# FPGA_Ground.net
KiCad netlist of a schematic drawn in Altium Designer
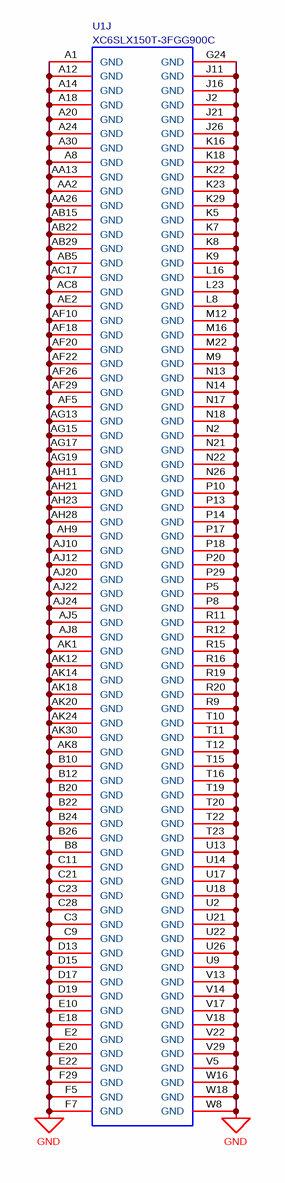
[diagram p0: FPGA_Ground.SchDoc]

(export (version "E")
  (design (tool "Eeschema 10.0.6"))
  (components
    (comp (ref "U1")
      (value "XC6SLX150T-3FGG900C")
      (footprint "MC_S6/BGA/FGG900")
      (fields (field (name "MANUFACTURER") "Xilinx Inc."))
      (libsource (lib "ALCT_MEZ_SPARTAN6_Library") (part "XC6SLX150T-3FGG900C"))
    )
  )
  (nets
    (net (code "1") (name "GND") (class "Default")
      (node (ref "U1") (pin "A1") (pinfunction "GND_A1") (pintype "power_in"))
      (node (ref "U1") (pin "A12") (pinfunction "GND_A12") (pintype "power_in"))
      (node (ref "U1") (pin "A14") (pinfunction "GND_A14") (pintype "power_in"))
      (node (ref "U1") (pin "A18") (pinfunction "GND_A18") (pintype "power_in"))
      (node (ref "U1") (pin "A20") (pinfunction "GND_A20") (pintype "power_in"))
      (node (ref "U1") (pin "A24") (pinfunction "GND_A24") (pintype "power_in"))
      (node (ref "U1") (pin "A30") (pinfunction "GND_A30") (pintype "power_in"))
      (node (ref "U1") (pin "A8") (pinfunction "GND_A8") (pintype "power_in"))
      (node (ref "U1") (pin "AA13") (pinfunction "GND_AA13") (pintype "power_in"))
      (node (ref "U1") (pin "AA2") (pinfunction "GND_AA2") (pintype "power_in"))
      (node (ref "U1") (pin "AA26") (pinfunction "GND_AA26") (pintype "power_in"))
      (node (ref "U1") (pin "AB15") (pinfunction "GND_AB15") (pintype "power_in"))
      (node (ref "U1") (pin "AB22") (pinfunction "GND_AB22") (pintype "power_in"))
      (node (ref "U1") (pin "AB29") (pinfunction "GND_AB29") (pintype "power_in"))
      (node (ref "U1") (pin "AB5") (pinfunction "GND_AB5") (pintype "power_in"))
      (node (ref "U1") (pin "AC17") (pinfunction "GND_AC17") (pintype "power_in"))
      (node (ref "U1") (pin "AC8") (pinfunction "GND_AC8") (pintype "power_in"))
      (node (ref "U1") (pin "AE2") (pinfunction "GND_AE2") (pintype "power_in"))
      (node (ref "U1") (pin "AF10") (pinfunction "GND_AF10") (pintype "power_in"))
      (node (ref "U1") (pin "AF18") (pinfunction "GND_AF18") (pintype "power_in"))
      (node (ref "U1") (pin "AF20") (pinfunction "GND_AF20") (pintype "power_in"))
      (node (ref "U1") (pin "AF22") (pinfunction "GND_AF22") (pintype "power_in"))
      (node (ref "U1") (pin "AF26") (pinfunction "GND_AF26") (pintype "power_in"))
      (node (ref "U1") (pin "AF29") (pinfunction "GND_AF29") (pintype "power_in"))
      (node (ref "U1") (pin "AF5") (pinfunction "GND_AF5") (pintype "power_in"))
      (node (ref "U1") (pin "AG13") (pinfunction "GND_AG13") (pintype "power_in"))
      (node (ref "U1") (pin "AG15") (pinfunction "GND_AG15") (pintype "power_in"))
      (node (ref "U1") (pin "AG17") (pinfunction "GND_AG17") (pintype "power_in"))
      (node (ref "U1") (pin "AG19") (pinfunction "GND_AG19") (pintype "power_in"))
      (node (ref "U1") (pin "AH11") (pinfunction "GND_AH11") (pintype "power_in"))
      (node (ref "U1") (pin "AH21") (pinfunction "GND_AH21") (pintype "power_in"))
      (node (ref "U1") (pin "AH23") (pinfunction "GND_AH23") (pintype "power_in"))
      (node (ref "U1") (pin "AH28") (pinfunction "GND_AH28") (pintype "power_in"))
      (node (ref "U1") (pin "AH9") (pinfunction "GND_AH9") (pintype "power_in"))
      (node (ref "U1") (pin "AJ10") (pinfunction "GND_AJ10") (pintype "power_in"))
      (node (ref "U1") (pin "AJ12") (pinfunction "GND_AJ12") (pintype "power_in"))
      (node (ref "U1") (pin "AJ20") (pinfunction "GND_AJ20") (pintype "power_in"))
      (node (ref "U1") (pin "AJ22") (pinfunction "GND_AJ22") (pintype "power_in"))
      (node (ref "U1") (pin "AJ24") (pinfunction "GND_AJ24") (pintype "power_in"))
      (node (ref "U1") (pin "AJ5") (pinfunction "GND_AJ5") (pintype "power_in"))
      (node (ref "U1") (pin "AJ8") (pinfunction "GND_AJ8") (pintype "power_in"))
      (node (ref "U1") (pin "AK1") (pinfunction "GND_AK1") (pintype "power_in"))
      (node (ref "U1") (pin "AK12") (pinfunction "GND_AK12") (pintype "power_in"))
      (node (ref "U1") (pin "AK14") (pinfunction "GND_AK14") (pintype "power_in"))
      (node (ref "U1") (pin "AK18") (pinfunction "GND_AK18") (pintype "power_in"))
      (node (ref "U1") (pin "AK20") (pinfunction "GND_AK20") (pintype "power_in"))
      (node (ref "U1") (pin "AK24") (pinfunction "GND_AK24") (pintype "power_in"))
      (node (ref "U1") (pin "AK30") (pinfunction "GND_AK30") (pintype "power_in"))
      (node (ref "U1") (pin "AK8") (pinfunction "GND_AK8") (pintype "power_in"))
      (node (ref "U1") (pin "B10") (pinfunction "GND_B10") (pintype "power_in"))
      (node (ref "U1") (pin "B12") (pinfunction "GND_B12") (pintype "power_in"))
      (node (ref "U1") (pin "B20") (pinfunction "GND_B20") (pintype "power_in"))
      (node (ref "U1") (pin "B22") (pinfunction "GND_B22") (pintype "power_in"))
      (node (ref "U1") (pin "B24") (pinfunction "GND_B24") (pintype "power_in"))
      (node (ref "U1") (pin "B26") (pinfunction "GND_B26") (pintype "power_in"))
      (node (ref "U1") (pin "B8") (pinfunction "GND_B8") (pintype "power_in"))
      (node (ref "U1") (pin "C11") (pinfunction "GND_C11") (pintype "power_in"))
      (node (ref "U1") (pin "C21") (pinfunction "GND_C21") (pintype "power_in"))
      (node (ref "U1") (pin "C23") (pinfunction "GND_C23") (pintype "power_in"))
      (node (ref "U1") (pin "C28") (pinfunction "GND_C28") (pintype "power_in"))
      (node (ref "U1") (pin "C3") (pinfunction "GND_C3") (pintype "power_in"))
      (node (ref "U1") (pin "C9") (pinfunction "GND_C9") (pintype "power_in"))
      (node (ref "U1") (pin "D13") (pinfunction "GND_D13") (pintype "power_in"))
      (node (ref "U1") (pin "D15") (pinfunction "GND_D15") (pintype "power_in"))
      (node (ref "U1") (pin "D17") (pinfunction "GND_D17") (pintype "power_in"))
      (node (ref "U1") (pin "D19") (pinfunction "GND_D19") (pintype "power_in"))
      (node (ref "U1") (pin "E10") (pinfunction "GND_E10") (pintype "power_in"))
      (node (ref "U1") (pin "E18") (pinfunction "GND_E18") (pintype "power_in"))
      (node (ref "U1") (pin "E2") (pinfunction "GND_E2") (pintype "power_in"))
      (node (ref "U1") (pin "E20") (pinfunction "GND_E20") (pintype "power_in"))
      (node (ref "U1") (pin "E22") (pinfunction "GND_E22") (pintype "power_in"))
      (node (ref "U1") (pin "F29") (pinfunction "GND_F29") (pintype "power_in"))
      (node (ref "U1") (pin "F5") (pinfunction "GND_F5") (pintype "power_in"))
      (node (ref "U1") (pin "F7") (pinfunction "GND_F7") (pintype "power_in"))
      (node (ref "U1") (pin "G24") (pinfunction "GND_G24") (pintype "power_in"))
      (node (ref "U1") (pin "J11") (pinfunction "GND_J11") (pintype "power_in"))
      (node (ref "U1") (pin "J16") (pinfunction "GND_J16") (pintype "power_in"))
      (node (ref "U1") (pin "J2") (pinfunction "GND_J2") (pintype "power_in"))
      (node (ref "U1") (pin "J21") (pinfunction "GND_J21") (pintype "power_in"))
      (node (ref "U1") (pin "J26") (pinfunction "GND_J26") (pintype "power_in"))
      (node (ref "U1") (pin "K16") (pinfunction "GND_K16") (pintype "power_in"))
      (node (ref "U1") (pin "K18") (pinfunction "GND_K18") (pintype "power_in"))
      (node (ref "U1") (pin "K22") (pinfunction "GND_K22") (pintype "power_in"))
      (node (ref "U1") (pin "K23") (pinfunction "GND_K23") (pintype "power_in"))
      (node (ref "U1") (pin "K29") (pinfunction "GND_K29") (pintype "power_in"))
      (node (ref "U1") (pin "K5") (pinfunction "GND_K5") (pintype "power_in"))
      (node (ref "U1") (pin "K7") (pinfunction "GND_K7") (pintype "power_in"))
      (node (ref "U1") (pin "K8") (pinfunction "GND_K8") (pintype "power_in"))
      (node (ref "U1") (pin "K9") (pinfunction "GND_K9") (pintype "power_in"))
      (node (ref "U1") (pin "L16") (pinfunction "GND_L16") (pintype "power_in"))
      (node (ref "U1") (pin "L23") (pinfunction "GND_L23") (pintype "power_in"))
      (node (ref "U1") (pin "L8") (pinfunction "GND_L8") (pintype "power_in"))
      (node (ref "U1") (pin "M12") (pinfunction "GND_M12") (pintype "power_in"))
      (node (ref "U1") (pin "M16") (pinfunction "GND_M16") (pintype "power_in"))
      (node (ref "U1") (pin "M22") (pinfunction "GND_M22") (pintype "power_in"))
      (node (ref "U1") (pin "M9") (pinfunction "GND_M9") (pintype "power_in"))
      (node (ref "U1") (pin "N13") (pinfunction "GND_N13") (pintype "power_in"))
      (node (ref "U1") (pin "N14") (pinfunction "GND_N14") (pintype "power_in"))
      (node (ref "U1") (pin "N17") (pinfunction "GND_N17") (pintype "power_in"))
      (node (ref "U1") (pin "N18") (pinfunction "GND_N18") (pintype "power_in"))
      (node (ref "U1") (pin "N2") (pinfunction "GND_N2") (pintype "power_in"))
      (node (ref "U1") (pin "N21") (pinfunction "GND_N21") (pintype "power_in"))
      (node (ref "U1") (pin "N22") (pinfunction "GND_N22") (pintype "power_in"))
      (node (ref "U1") (pin "N26") (pinfunction "GND_N26") (pintype "power_in"))
      (node (ref "U1") (pin "P10") (pinfunction "GND_P10") (pintype "power_in"))
      (node (ref "U1") (pin "P13") (pinfunction "GND_P13") (pintype "power_in"))
      (node (ref "U1") (pin "P14") (pinfunction "GND_P14") (pintype "power_in"))
      (node (ref "U1") (pin "P17") (pinfunction "GND_P17") (pintype "power_in"))
      (node (ref "U1") (pin "P18") (pinfunction "GND_P18") (pintype "power_in"))
      (node (ref "U1") (pin "P20") (pinfunction "GND_P20") (pintype "power_in"))
      (node (ref "U1") (pin "P29") (pinfunction "GND_P29") (pintype "power_in"))
      (node (ref "U1") (pin "P5") (pinfunction "GND_P5") (pintype "power_in"))
      (node (ref "U1") (pin "P8") (pinfunction "GND_P8") (pintype "power_in"))
      (node (ref "U1") (pin "R11") (pinfunction "GND_R11") (pintype "power_in"))
      (node (ref "U1") (pin "R12") (pinfunction "GND_R12") (pintype "power_in"))
      (node (ref "U1") (pin "R15") (pinfunction "GND_R15") (pintype "power_in"))
      (node (ref "U1") (pin "R16") (pinfunction "GND_R16") (pintype "power_in"))
      (node (ref "U1") (pin "R19") (pinfunction "GND_R19") (pintype "power_in"))
      (node (ref "U1") (pin "R20") (pinfunction "GND_R20") (pintype "power_in"))
      (node (ref "U1") (pin "R9") (pinfunction "GND_R9") (pintype "power_in"))
      (node (ref "U1") (pin "T10") (pinfunction "GND_T10") (pintype "power_in"))
      (node (ref "U1") (pin "T11") (pinfunction "GND_T11") (pintype "power_in"))
      (node (ref "U1") (pin "T12") (pinfunction "GND_T12") (pintype "power_in"))
      (node (ref "U1") (pin "T15") (pinfunction "GND_T15") (pintype "power_in"))
      (node (ref "U1") (pin "T16") (pinfunction "GND_T16") (pintype "power_in"))
      (node (ref "U1") (pin "T19") (pinfunction "GND_T19") (pintype "power_in"))
      (node (ref "U1") (pin "T20") (pinfunction "GND_T20") (pintype "power_in"))
      (node (ref "U1") (pin "T22") (pinfunction "GND_T22") (pintype "power_in"))
      (node (ref "U1") (pin "T23") (pinfunction "GND_T23") (pintype "power_in"))
      (node (ref "U1") (pin "U13") (pinfunction "GND_U13") (pintype "power_in"))
      (node (ref "U1") (pin "U14") (pinfunction "GND_U14") (pintype "power_in"))
      (node (ref "U1") (pin "U17") (pinfunction "GND_U17") (pintype "power_in"))
      (node (ref "U1") (pin "U18") (pinfunction "GND_U18") (pintype "power_in"))
      (node (ref "U1") (pin "U2") (pinfunction "GND_U2") (pintype "power_in"))
      (node (ref "U1") (pin "U21") (pinfunction "GND_U21") (pintype "power_in"))
      (node (ref "U1") (pin "U22") (pinfunction "GND_U22") (pintype "power_in"))
      (node (ref "U1") (pin "U26") (pinfunction "GND_U26") (pintype "power_in"))
      (node (ref "U1") (pin "U9") (pinfunction "GND_U9") (pintype "power_in"))
      (node (ref "U1") (pin "V13") (pinfunction "GND_V13") (pintype "power_in"))
      (node (ref "U1") (pin "V14") (pinfunction "GND_V14") (pintype "power_in"))
      (node (ref "U1") (pin "V17") (pinfunction "GND_V17") (pintype "power_in"))
      (node (ref "U1") (pin "V18") (pinfunction "GND_V18") (pintype "power_in"))
      (node (ref "U1") (pin "V22") (pinfunction "GND_V22") (pintype "power_in"))
      (node (ref "U1") (pin "V29") (pinfunction "GND_V29") (pintype "power_in"))
      (node (ref "U1") (pin "V5") (pinfunction "GND_V5") (pintype "power_in"))
      (node (ref "U1") (pin "W16") (pinfunction "GND_W16") (pintype "power_in"))
      (node (ref "U1") (pin "W18") (pinfunction "GND_W18") (pintype "power_in"))
      (node (ref "U1") (pin "W8") (pinfunction "GND_W8") (pintype "power_in"))
    )
  )
)
